# cap.net
KiCad netlist of a schematic drawn in EAGLE
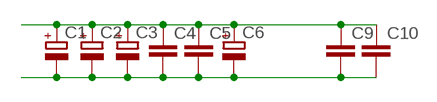
[diagram p0: schematic, sheet 1]

(export (version "E")
  (design (tool "Eeschema 10.0.6"))
  (components
    (comp (ref "C1")
      (value "CPOL-EUE7.5-18")
      (footprint "eagle-import:E7,5-18")
      (libsource (lib "eagle-import") (part "CPOL-EUE7.5-18"))
    )
    (comp (ref "C2")
      (value "CPOL-EUE7.5-18")
      (footprint "eagle-import:E7,5-18")
      (libsource (lib "eagle-import") (part "CPOL-EUE7.5-18"))
    )
    (comp (ref "C3")
      (value "CPOL-EUE7.5-18")
      (footprint "eagle-import:E7,5-18")
      (libsource (lib "eagle-import") (part "CPOL-EUE7.5-18"))
    )
    (comp (ref "C4")
      (value "C-EU075-052X106")
      (footprint "eagle-import:C075-052X106")
      (libsource (lib "eagle-import") (part "C-EU075-052X106"))
    )
    (comp (ref "C5")
      (value "C-EU075-052X106")
      (footprint "eagle-import:C075-052X106")
      (libsource (lib "eagle-import") (part "C-EU075-052X106"))
    )
    (comp (ref "C6")
      (value "CPOL-EUE7.5-18")
      (footprint "eagle-import:E7,5-18")
      (libsource (lib "eagle-import") (part "CPOL-EUE7.5-18"))
    )
    (comp (ref "C9")
      (value "C-EU075-052X106")
      (footprint "eagle-import:C075-052X106")
      (libsource (lib "eagle-import") (part "C-EU075-052X106"))
    )
    (comp (ref "C10")
      (value "C-EU075-052X106")
      (footprint "eagle-import:C075-052X106")
      (libsource (lib "eagle-import") (part "C-EU075-052X106"))
    )
  )
  (nets
    (net (code "1") (name "Net-(C1-Pad+)") (class "Default")
      (node (ref "C1") (pin "+") (pinfunction "+_+") (pintype "passive"))
      (node (ref "C10") (pin "1") (pinfunction "1_1") (pintype "passive"))
      (node (ref "C2") (pin "+") (pinfunction "+_+") (pintype "passive"))
      (node (ref "C3") (pin "+") (pinfunction "+_+") (pintype "passive"))
      (node (ref "C4") (pin "1") (pinfunction "1_1") (pintype "passive"))
      (node (ref "C5") (pin "1") (pinfunction "1_1") (pintype "passive"))
      (node (ref "C6") (pin "+") (pinfunction "+_+") (pintype "passive"))
      (node (ref "C9") (pin "1") (pinfunction "1_1") (pintype "passive"))
    )
    (net (code "2") (name "Net-(C1-Pad-)") (class "Default")
      (node (ref "C1") (pin "-") (pinfunction "-_-") (pintype "passive"))
      (node (ref "C10") (pin "2") (pinfunction "2_2") (pintype "passive"))
      (node (ref "C2") (pin "-") (pinfunction "-_-") (pintype "passive"))
      (node (ref "C3") (pin "-") (pinfunction "-_-") (pintype "passive"))
      (node (ref "C4") (pin "2") (pinfunction "2_2") (pintype "passive"))
      (node (ref "C5") (pin "2") (pinfunction "2_2") (pintype "passive"))
      (node (ref "C6") (pin "-") (pinfunction "-_-") (pintype "passive"))
      (node (ref "C9") (pin "2") (pinfunction "2_2") (pintype "passive"))
    )
  )
)
